# POWERSYSTEM.net
KiCad netlist of a schematic drawn in Altium Designer
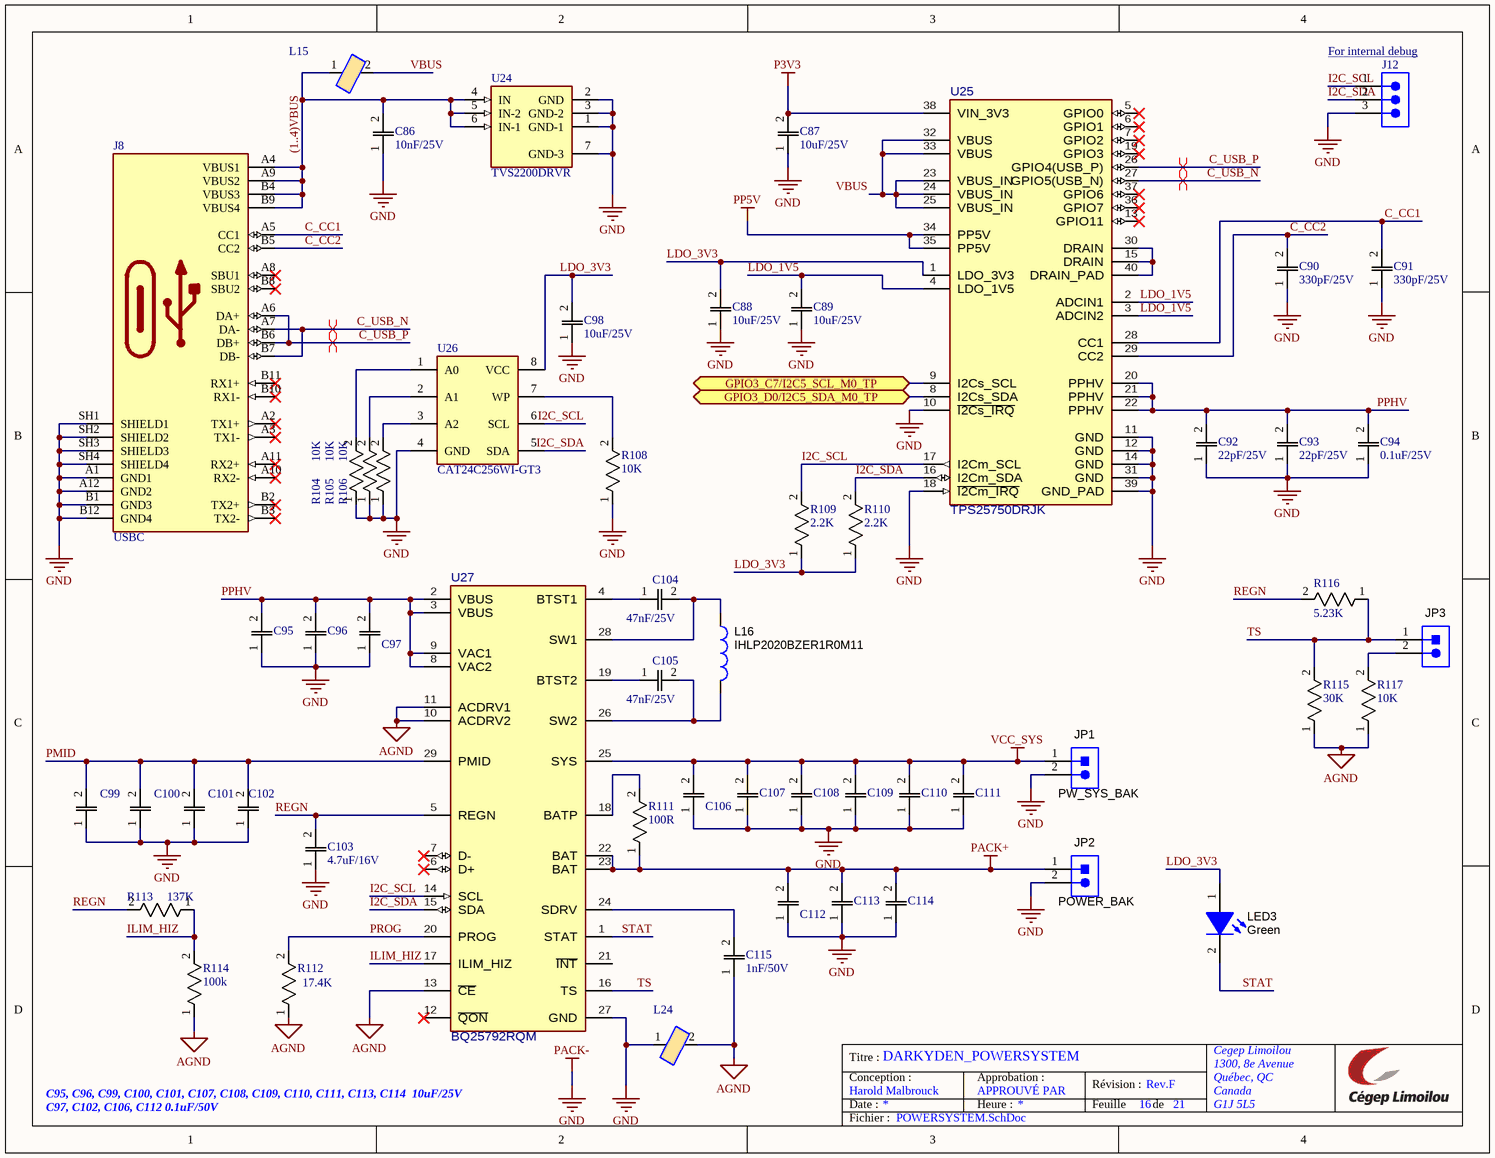
[diagram p0: POWERSYSTEM.SchDoc]

(export (version "E")
  (design (tool "Eeschema 10.0.6"))
  (components
    (comp (ref "C86")
      (value "10nF/25V")
      (footprint "C0805")
      (description "0.01uF 25V X7R 10% SMD 0805 125C Paper T/R")
      (fields
        (field (name "MOUSER PART NUMBER") "80-C0805C103K3R")
        (field (name "ARROW PART NUMBER") "C0805C103K3RACTU")
      )
      (libsource (lib "DARKYDEN") (part "C0805C103K3RACTU"))
    )
    (comp (ref "C87")
      (value "10uF/25V")
      (footprint "C0805")
      (description "10uF / 25 VDC, +85degC, X5R Dielec, +/-10% ¦ KEMET C0805C106K3PACTU 0805")
      (fields
        (field (name "MANUFACTURER") "KEMET")
        (field (name "MANUFACTURER PART NUMBER") "C0805C106K3PACTU")
      )
      (libsource (lib "DARKYDEN") (part "C0805C106K3PACTU"))
    )
    (comp (ref "C88")
      (value "10uF/25V")
      (footprint "C0805")
      (description "10uF / 25 VDC, +85degC, X5R Dielec, +/-10% ¦ KEMET C0805C106K3PACTU 0805")
      (fields
        (field (name "MANUFACTURER") "KEMET")
        (field (name "MANUFACTURER PART NUMBER") "C0805C106K3PACTU")
      )
      (libsource (lib "DARKYDEN") (part "C0805C106K3PACTU"))
    )
    (comp (ref "C89")
      (value "10uF/25V")
      (footprint "C0805")
      (description "10uF / 25 VDC, +85degC, X5R Dielec, +/-10% ¦ KEMET C0805C106K3PACTU 0805")
      (fields
        (field (name "MANUFACTURER") "KEMET")
        (field (name "MANUFACTURER PART NUMBER") "C0805C106K3PACTU")
      )
      (libsource (lib "DARKYDEN") (part "C0805C106K3PACTU"))
    )
    (comp (ref "C90")
      (value "330pF/25V")
      (footprint "SamacSys:C0805")
      (description "330pF 25VC0G 0805 10%")
      (fields (field (name "MOUSER PART NUMBER") "80-C0805C331K3G") (field (name "MANUFACTURER") "KEMET"))
      (libsource (lib "DARKYDEN") (part "C0805C331K3GACTU"))
    )
    (comp (ref "C91")
      (value "330pF/25V")
      (footprint "SamacSys:C0805")
      (description "330pF 25VC0G 0805 10%")
      (fields (field (name "MOUSER PART NUMBER") "80-C0805C331K3G") (field (name "MANUFACTURER") "KEMET"))
      (libsource (lib "DARKYDEN") (part "C0805C331K3GACTU"))
    )
    (comp (ref "C92")
      (value "22pF/25V")
      (footprint "c0805")
      (description "22uF/25V 20% X5R 0805")
      (fields
        (field (name "MOUSER PART NUMBER") "187-CL21A226MAYNNNE")
        (field (name "ARROW PART NUMBER") "CL21A226MAYNNNE")
      )
      (libsource (lib "DARKYDEN") (part "CL21A226MAYNNNE"))
    )
    (comp (ref "C93")
      (value "22pF/25V")
      (footprint "c0805")
      (description "22uF/25V 20% X5R 0805")
      (fields
        (field (name "MOUSER PART NUMBER") "187-CL21A226MAYNNNE")
        (field (name "ARROW PART NUMBER") "CL21A226MAYNNNE")
      )
      (libsource (lib "DARKYDEN") (part "CL21A226MAYNNNE"))
    )
    (comp (ref "C94")
      (value "0.1uF/25V")
      (footprint "c0805")
      (description "0.1uF 25V X7R 10% SMD 0805 125C Plastic T/R")
      (fields
        (field (name "MANUFACTURER") "KEMET")
        (field (name "MANUFACTURER PART NUMBER") "C0805C104K5RACTU")
      )
      (libsource (lib "DARKYDEN") (part "C0805C104K3RACTU"))
    )
    (comp (ref "C95")
      (value "10uF/25V")
      (footprint "C0805")
      (description "10uF / 25 VDC, +85degC, X5R Dielec, +/-10% ¦ KEMET C0805C106K3PACTU 0805")
      (fields
        (field (name "MANUFACTURER") "KEMET")
        (field (name "MANUFACTURER PART NUMBER") "C0805C106K3PACTU")
      )
      (libsource (lib "DARKYDEN") (part "C0805C106K3PACTU"))
    )
    (comp (ref "C96")
      (value "10uF/25V")
      (footprint "C0805")
      (description "10uF / 25 VDC, +85degC, X5R Dielec, +/-10% ¦ KEMET C0805C106K3PACTU 0805")
      (fields
        (field (name "MANUFACTURER") "KEMET")
        (field (name "MANUFACTURER PART NUMBER") "C0805C106K3PACTU")
      )
      (libsource (lib "DARKYDEN") (part "C0805C106K3PACTU"))
    )
    (comp (ref "C97")
      (value "0.1uF/50V")
      (footprint "C0805")
      (description "0.1uF/50V X7R 10% 0805 Multilayer Ceramic Capacitors Mlcc Smd/Smt Rohs")
      (fields
        (field (name "MOUSER PART NUMBER") "80-C0805C104K5R")
        (field (name "ARROW PART NUMBER") "C0805C104K5RACTU")
      )
      (libsource (lib "DARKYDEN") (part "C0805C104K5RACTU"))
    )
    (comp (ref "C98")
      (value "10uF/25V")
      (footprint "C0805")
      (description "10uF / 25 VDC, +85degC, X5R Dielec, +/-10% ¦ KEMET C0805C106K3PACTU 0805")
      (fields
        (field (name "MANUFACTURER") "KEMET")
        (field (name "MANUFACTURER PART NUMBER") "C0805C106K3PACTU")
      )
      (libsource (lib "DARKYDEN") (part "C0805C106K3PACTU"))
    )
    (comp (ref "C99")
      (value "10uF/25V")
      (footprint "C0805")
      (description "10uF / 25 VDC, +85degC, X5R Dielec, +/-10% ¦ KEMET C0805C106K3PACTU 0805")
      (fields
        (field (name "MANUFACTURER") "KEMET")
        (field (name "MANUFACTURER PART NUMBER") "C0805C106K3PACTU")
      )
      (libsource (lib "DARKYDEN") (part "C0805C106K3PACTU"))
    )
    (comp (ref "C100")
      (value "10uF/25V")
      (footprint "C0805")
      (description "10uF / 25 VDC, +85degC, X5R Dielec, +/-10% ¦ KEMET C0805C106K3PACTU 0805")
      (fields
        (field (name "MANUFACTURER") "KEMET")
        (field (name "MANUFACTURER PART NUMBER") "C0805C106K3PACTU")
      )
      (libsource (lib "DARKYDEN") (part "C0805C106K3PACTU"))
    )
    (comp (ref "C101")
      (value "10uF/25V")
      (footprint "C0805")
      (description "10uF / 25 VDC, +85degC, X5R Dielec, +/-10% ¦ KEMET C0805C106K3PACTU 0805")
      (fields
        (field (name "MANUFACTURER") "KEMET")
        (field (name "MANUFACTURER PART NUMBER") "C0805C106K3PACTU")
      )
      (libsource (lib "DARKYDEN") (part "C0805C106K3PACTU"))
    )
    (comp (ref "C102")
      (value "0.1uF/50V")
      (footprint "C0805")
      (description "0.1uF/50V X7R 10% 0805 Multilayer Ceramic Capacitors Mlcc Smd/Smt Rohs")
      (fields
        (field (name "MOUSER PART NUMBER") "80-C0805C104K5R")
        (field (name "ARROW PART NUMBER") "C0805C104K5RACTU")
      )
      (libsource (lib "DARKYDEN") (part "C0805C104K5RACTU"))
    )
    (comp (ref "C103")
      (value "4.7uF/16V")
      (footprint "C0805")
      (description "4.7 uF, 16 V, ± 10%, X7R, 0805 [2012 Metric]")
      (fields
        (field (name "MOUSER PART NUMBER") "80-C0805C475K4R")
        (field (name "ARROW PART NUMBER") "C0805C475K4RACTU")
      )
      (libsource (lib "DARKYDEN") (part "C0805C475K4RACTU"))
    )
    (comp (ref "C104")
      (value "47nF/25V")
      (footprint "C0805")
      (description "47nF/25V C0G 10% Pad SMD 0805 125C Extreme Low ESR T/R")
      (fields
        (field (name "MOUSER PART NUMBER") "80-C0805C473K3G")
        (field (name "ARROW PART NUMBER") "C0805C473K3GACTU")
      )
      (libsource (lib "DARKYDEN") (part "C0805C473K3GACTU"))
    )
    (comp (ref "C105")
      (value "47nF/25V")
      (footprint "C0805")
      (description "47nF/25V C0G 10% Pad SMD 0805 125C Extreme Low ESR T/R")
      (fields
        (field (name "MOUSER PART NUMBER") "80-C0805C473K3G")
        (field (name "ARROW PART NUMBER") "C0805C473K3GACTU")
      )
      (libsource (lib "DARKYDEN") (part "C0805C473K3GACTU"))
    )
    (comp (ref "C106")
      (value "0.1uF/50V")
      (footprint "C0805")
      (description "0.1uF/50V X7R 10% 0805 Multilayer Ceramic Capacitors Mlcc Smd/Smt Rohs")
      (fields
        (field (name "MOUSER PART NUMBER") "80-C0805C104K5R")
        (field (name "ARROW PART NUMBER") "C0805C104K5RACTU")
      )
      (libsource (lib "DARKYDEN") (part "C0805C104K5RACTU"))
    )
    (comp (ref "C107")
      (value "10uF/25V")
      (footprint "C0805")
      (description "10uF / 25 VDC, +85degC, X5R Dielec, +/-10% ¦ KEMET C0805C106K3PACTU 0805")
      (fields
        (field (name "MANUFACTURER") "KEMET")
        (field (name "MANUFACTURER PART NUMBER") "C0805C106K3PACTU")
      )
      (libsource (lib "DARKYDEN") (part "C0805C106K3PACTU"))
    )
    (comp (ref "C108")
      (value "10uF/25V")
      (footprint "C0805")
      (description "10uF / 25 VDC, +85degC, X5R Dielec, +/-10% ¦ KEMET C0805C106K3PACTU 0805")
      (fields
        (field (name "MANUFACTURER") "KEMET")
        (field (name "MANUFACTURER PART NUMBER") "C0805C106K3PACTU")
      )
      (libsource (lib "DARKYDEN") (part "C0805C106K3PACTU"))
    )
    (comp (ref "C109")
      (value "10uF/25V")
      (footprint "C0805")
      (description "10uF / 25 VDC, +85degC, X5R Dielec, +/-10% ¦ KEMET C0805C106K3PACTU 0805")
      (fields
        (field (name "MANUFACTURER") "KEMET")
        (field (name "MANUFACTURER PART NUMBER") "C0805C106K3PACTU")
      )
      (libsource (lib "DARKYDEN") (part "C0805C106K3PACTU"))
    )
    (comp (ref "C110")
      (value "10uF/25V")
      (footprint "C0805")
      (description "10uF / 25 VDC, +85degC, X5R Dielec, +/-10% ¦ KEMET C0805C106K3PACTU 0805")
      (fields
        (field (name "MANUFACTURER") "KEMET")
        (field (name "MANUFACTURER PART NUMBER") "C0805C106K3PACTU")
      )
      (libsource (lib "DARKYDEN") (part "C0805C106K3PACTU"))
    )
    (comp (ref "C111")
      (value "10uF/25V")
      (footprint "C0805")
      (description "10uF / 25 VDC, +85degC, X5R Dielec, +/-10% ¦ KEMET C0805C106K3PACTU 0805")
      (fields
        (field (name "MANUFACTURER") "KEMET")
        (field (name "MANUFACTURER PART NUMBER") "C0805C106K3PACTU")
      )
      (libsource (lib "DARKYDEN") (part "C0805C106K3PACTU"))
    )
    (comp (ref "C112")
      (value "0.1uF/50V")
      (footprint "C0805")
      (description "0.1uF/50V X7R 10% 0805 Multilayer Ceramic Capacitors Mlcc Smd/Smt Rohs")
      (fields
        (field (name "MOUSER PART NUMBER") "80-C0805C104K5R")
        (field (name "ARROW PART NUMBER") "C0805C104K5RACTU")
      )
      (libsource (lib "DARKYDEN") (part "C0805C104K5RACTU"))
    )
    (comp (ref "C113")
      (value "10uF/25V")
      (footprint "C0805")
      (description "10uF / 25 VDC, +85degC, X5R Dielec, +/-10% ¦ KEMET C0805C106K3PACTU 0805")
      (fields
        (field (name "MANUFACTURER") "KEMET")
        (field (name "MANUFACTURER PART NUMBER") "C0805C106K3PACTU")
      )
      (libsource (lib "DARKYDEN") (part "C0805C106K3PACTU"))
    )
    (comp (ref "C114")
      (value "10uF/25V")
      (footprint "C0805")
      (description "10uF / 25 VDC, +85degC, X5R Dielec, +/-10% ¦ KEMET C0805C106K3PACTU 0805")
      (fields
        (field (name "MANUFACTURER") "KEMET")
        (field (name "MANUFACTURER PART NUMBER") "C0805C106K3PACTU")
      )
      (libsource (lib "DARKYDEN") (part "C0805C106K3PACTU"))
    )
    (comp (ref "C115")
      (value "1nF/50V")
      (footprint "C0805")
      (description "Multilayer Ceramic Capacitor 1000 Pf 50 V ½ 10% X7R 0805 [2012 Metric]")
      (fields
        (field (name "MANUFACTURER") "KEMET")
        (field (name "MANUFACTURER PART NUMBER") "C0805C102K5RACTU")
      )
      (libsource (lib "DARKYDEN") (part "C0805C102K5RACTU"))
    )
    (comp (ref "J8")
      (value "USBC")
      (footprint "USB_C")
      (fields (field (name "MF") "Molex") (field (name "MP") "2012670005"))
      (libsource (lib "DARKYDEN") (part "USBC"))
    )
    (comp (ref "J12")
      (value "61300311121")
      (footprint "61300311121")
      (description "WR-PHD Pin Header, THT, Vertical, pitch 2.54mm, 1 Row, 3P")
      (fields (field (name "MANUFACTURER") "Wurth Elektronik"))
      (libsource (lib "Header") (part "61300311121"))
    )
    (comp (ref "JP1")
      (value "PW_SYS_BAK")
      (footprint "61300211121")
      (description "Header, 100mil, 2x1, Tin, TH")
      (fields
        (field (name "PARTNUMBER") "PEC02SAAN")
        (field (name "MANUFACTURER") "Sullins Connector Solutions")
        (field (name "PUBLISHER") "Texas Instruments")
      )
      (libsource (lib "texas_instrument_power") (part "Header_2x1"))
    )
    (comp (ref "JP2")
      (value "POWER_BAK")
      (footprint "61300211121")
      (description "Header, 100mil, 2x1, Tin, TH")
      (fields
        (field (name "PARTNUMBER") "PEC02SAAN")
        (field (name "MANUFACTURER") "Sullins Connector Solutions")
        (field (name "PUBLISHER") "Texas Instruments")
      )
      (libsource (lib "texas_instrument_power") (part "Header_2x1"))
    )
    (comp (ref "JP3")
      (value "TS")
      (footprint "61300211121")
      (description "Header, 100mil, 2x1, Tin, TH")
      (fields
        (field (name "PARTNUMBER") "PEC02SAAN")
        (field (name "MANUFACTURER") "Sullins Connector Solutions")
        (field (name "PUBLISHER") "Texas Instruments")
      )
      (libsource (lib "texas_instrument_power") (part "Header_2x1"))
    )
    (comp (ref "L15")
      (value "FBMJ2125HM210NT")
      (footprint "INDC2012X105N")
      (description "Ferrite Beads Power Chip 21Ohm 30% 100MHz 6A 0.004Ohm DCR 0805 Automotive T/R")
      (fields
        (field (name "MANUFACTURER") "Taiyo Yuden")
        (field (name "MOUSER PART NUMBER") "963-FBMJ2125HM210NT")
      )
      (libsource (lib "SamacSys") (part "FBMJ2125HM210NT"))
    )
    (comp (ref "L16")
      (value "IHLP2020BZER1R0M11")
      (footprint "IHLP-2020BZ")
      (description "Inductor, Shielded Drum Core, Powdered Iron, 1 uH, 7 A, 0.0181 ohm, SMD")
      (fields (field (name "MANUFACTURER") "Vishay-Dale") (field (name "PUBLISHER") "Texas Instruments"))
      (libsource (lib "texas_instrument_power") (part "IHLP2020BZER1R0M11"))
    )
    (comp (ref "L24")
      (value "FBMJ2125HM210NT")
      (footprint "INDC2012X105N")
      (description "Ferrite Beads Power Chip 21Ohm 30% 100MHz 6A 0.004Ohm DCR 0805 Automotive T/R")
      (fields
        (field (name "MANUFACTURER") "Taiyo Yuden")
        (field (name "MOUSER PART NUMBER") "963-FBMJ2125HM210NT")
      )
      (libsource (lib "SamacSys") (part "FBMJ2125HM210NT"))
    )
    (comp (ref "LED3")
      (value "Green")
      (footprint "LED_LTST-C190")
      (description "LED, Green, SMD")
      (fields (field (name "MANUFACTURER") "Lite-On") (field (name "PARTNUMBER") "LTST-C190GKT"))
      (libsource (lib "PD_BQ_Ref_Design") (part "LED_Gr_SMD"))
    )
    (comp (ref "R104")
      (value "10K")
      (footprint "SamacSys:RESC1608X55N")
      (description "10K Ohm 5% Res Thick Film 0603  0.1W(1/10W) ±200ppm/C Pad SMD Automotive T/R")
      (fields
        (field (name "MOUSER PART NUMBER") "667-ERJ-3GEYJ103V")
        (field (name "ARROW PART NUMBER") "ERJ-3GEYJ103V")
      )
      (libsource (lib "DARKYDEN") (part "ERJ-3GEYJ103V"))
    )
    (comp (ref "R105")
      (value "10K")
      (footprint "SamacSys:RESC1608X55N")
      (description "10K Ohm 5% Res Thick Film 0603  0.1W(1/10W) ±200ppm/C Pad SMD Automotive T/R")
      (fields
        (field (name "MOUSER PART NUMBER") "667-ERJ-3GEYJ103V")
        (field (name "ARROW PART NUMBER") "ERJ-3GEYJ103V")
      )
      (libsource (lib "DARKYDEN") (part "ERJ-3GEYJ103V"))
    )
    (comp (ref "R106")
      (value "10K")
      (footprint "SamacSys:RESC1608X55N")
      (description "10K Ohm 5% Res Thick Film 0603  0.1W(1/10W) ±200ppm/C Pad SMD Automotive T/R")
      (fields
        (field (name "MOUSER PART NUMBER") "667-ERJ-3GEYJ103V")
        (field (name "ARROW PART NUMBER") "ERJ-3GEYJ103V")
      )
      (libsource (lib "DARKYDEN") (part "ERJ-3GEYJ103V"))
    )
    (comp (ref "R108")
      (value "10K")
      (footprint "SamacSys:RESC1608X55N")
      (description "10K Ohm 5% Res Thick Film 0603  0.1W(1/10W) ±200ppm/C Pad SMD Automotive T/R")
      (fields
        (field (name "MOUSER PART NUMBER") "667-ERJ-3GEYJ103V")
        (field (name "ARROW PART NUMBER") "ERJ-3GEYJ103V")
      )
      (libsource (lib "DARKYDEN") (part "ERJ-3GEYJ103V"))
    )
    (comp (ref "R109")
      (value "2.2K")
      (footprint "SamacSys:RESC1608X55N")
      (description "2.2 kOhm, ï¿½ 5%, 100 mW, 0603 [1608 Metric], Thick Film, General Purpose")
      (fields
        (field (name "MOUSER PART NUMBER") "667-ERJ-3GEYJ222V")
        (field (name "ARROW PART NUMBER") "ERJ-3GEYJ222V")
      )
      (libsource (lib "DARKYDEN") (part "ERJ-3GEYJ222V"))
    )
    (comp (ref "R110")
      (value "2.2K")
      (footprint "SamacSys:RESC1608X55N")
      (description "2.2 kOhm, ï¿½ 5%, 100 mW, 0603 [1608 Metric], Thick Film, General Purpose")
      (fields
        (field (name "MOUSER PART NUMBER") "667-ERJ-3GEYJ222V")
        (field (name "ARROW PART NUMBER") "ERJ-3GEYJ222V")
      )
      (libsource (lib "DARKYDEN") (part "ERJ-3GEYJ222V"))
    )
    (comp (ref "R111")
      (value "100R")
      (footprint "SamacSys:RESC1608X55N")
      (description "100 Ohm 1% 1/10W 0603 ±100ppm/°C Molded SMD Punched Carrier T/R")
      (fields
        (field (name "MOUSER PART NUMBER") "667-ERJ-3EKF1000V")
        (field (name "ARROW PART NUMBER") "ERJ-3EKF1000V")
      )
      (libsource (lib "DARKYDEN") (part "ERJ-3EKF1000V"))
    )
    (comp (ref "R112")
      (value "17.4K")
      (footprint "SamacSys:RESC1608X55N")
      (description "17.4K Ohm 1% 1/10W +/-100ppm/ßC Molded Res Thick Film 0603  SMD Punched Carrier T/R")
      (fields
        (field (name "MOUSER PART NUMBER") "667-ERJ-3EKF1742V")
        (field (name "ARROW PART NUMBER") "ERJ-3EKF1742V")
      )
      (libsource (lib "DARKYDEN") (part "ERJ-3EKF1742V"))
    )
    (comp (ref "R113")
      (value "137K")
      (footprint "SamacSys:RESC1608X55N")
      (description "137K Ohm 1% 1/10W Res Thick Film 0603 ±100ppm/°C SMD Punched Carrier T/R")
      (fields
        (field (name "MOUSER PART NUMBER") "667-ERJ-3EKF1373V")
        (field (name "ARROW PART NUMBER") "ERJ-3EKF1373V")
      )
      (libsource (lib "DARKYDEN") (part "ERJ-3EKF1373V"))
    )
    (comp (ref "R114")
      (value "100k")
      (footprint "SamacSys:RESC1608X55N")
      (description "100K Ohm 5%  Res Thick Film 0603 1/10W +/-200ppm/ßC Molded SMD Punched Carrier T/R")
      (fields
        (field (name "MOUSER PART NUMBER") "667-ERJ-3GEYJ104V")
        (field (name "ARROW PART NUMBER") "ERJ-3GEYJ104V")
      )
      (libsource (lib "DARKYDEN") (part "ERJ-3GEYJ104V"))
    )
    (comp (ref "R115")
      (value "30K")
      (footprint "SamacSys:RESC1608X55N")
      (description "30K Ohm 5% 0.1W(1/10W) +/-200ppm/ßC Res Thick Film 0603  SMD Automotive T/R")
      (fields
        (field (name "MOUSER PART NUMBER") "667-ERJ-3GEYJ303V")
        (field (name "MANUFACTURER") "Panasonic")
      )
      (libsource (lib "DARKYDEN") (part "ERJ-3GEYJ303V"))
    )
    (comp (ref "R116")
      (value "5.23K")
      (footprint "SamacSys:RESC1608X55N")
      (description "5.23K Ohm 1% 1/10W Res Thick Film 0603+/-100ppm/ßC Molded SMD Punched Carrier T/R")
      (fields
        (field (name "MOUSER PART NUMBER") "667-ERJ-3EKF5231V")
        (field (name "ARROW PART NUMBER") "ERJ-3EKF5231V")
      )
      (libsource (lib "DARKYDEN") (part "ERJ-3EKF5231V"))
    )
    (comp (ref "R117")
      (value "10K")
      (footprint "SamacSys:RESC1608X55N")
      (description "10K Ohm 5% Res Thick Film 0603  0.1W(1/10W) ±200ppm/C Pad SMD Automotive T/R")
      (fields
        (field (name "MOUSER PART NUMBER") "667-ERJ-3GEYJ103V")
        (field (name "ARROW PART NUMBER") "ERJ-3GEYJ103V")
      )
      (libsource (lib "DARKYDEN") (part "ERJ-3GEYJ103V"))
    )
    (comp (ref "U24")
      (value "TVS2200DRVR")
      (footprint "SON65P200X200X80-7N")
      (description "ESD Suppressors / TVS Diodes 22V flat-clamp surge protection device 6-WSON -40 to 125")
      (fields (field (name "MF") "Texas Instruments"))
      (libsource (lib "TVS2200") (part "TVS2200DRVR"))
    )
    (comp (ref "U25")
      (value "TPS25750DRJK")
      (footprint "RJK0038B-C01-MFG")
      (description "USB Type-C and USB PD Controller with Integrated Power Switches Optimized for Power Applications")
      (fields (field (name "MANUFACTURER") "Texas Instruments"))
      (libsource (lib "PD_BQ_Ref_Design") (part "TPS25750DRJK"))
    )
    (comp (ref "U26")
      (value "CAT24C256WI-GT3")
      (footprint "SOIC127P600X175-8N")
      (description "EEPROM Memory IC 256Kbit I2C 1 MHz 500 ns 8-SOIC")
      (fields (field (name "MOUSER PART NUMBER") "698-CAT24C256WI-GT3"))
      (libsource (lib "SamacSys") (part "CAT24C256WI-GT3"))
    )
    (comp (ref "U27")
      (value "BQ25792RQM")
      (footprint "RQM0029A-MFG")
      (description "BQ2579x HotRod")
      (fields (field (name "MANUFACTURER") "Texas Instruments"))
      (libsource (lib "PD_BQ_Ref_Design") (part "BQ2579x"))
    )
  )
  (nets
    (net (code "1") (name "/(1..4)VBUS") (class "Default")
      (node (ref "C86") (pin "2") (pinfunction "2_2") (pintype "passive"))
      (node (ref "J8") (pin "A4") (pinfunction "VBUS1_A4") (pintype "power_in"))
      (node (ref "J8") (pin "A9") (pinfunction "VBUS2_A9") (pintype "power_in"))
      (node (ref "J8") (pin "B4") (pinfunction "VBUS3_B4") (pintype "power_in"))
      (node (ref "J8") (pin "B9") (pinfunction "VBUS4_B9") (pintype "power_in"))
      (node (ref "L15") (pin "1") (pinfunction "1_1") (pintype "passive"))
      (node (ref "U24") (pin "4") (pinfunction "IN_4") (pintype "input"))
      (node (ref "U24") (pin "5") (pinfunction "IN-2_5") (pintype "input"))
      (node (ref "U24") (pin "6") (pinfunction "IN-1_6") (pintype "input"))
    )
    (net (code "2") (name "/C_CC1") (class "Default")
      (node (ref "C91") (pin "2") (pinfunction "2_2") (pintype "passive"))
      (node (ref "J8") (pin "A5") (pinfunction "CC1_A5") (pintype "bidirectional"))
      (node (ref "U25") (pin "28") (pinfunction "CC1_28") (pintype "passive"))
    )
    (net (code "3") (name "/C_CC2") (class "Default")
      (node (ref "C90") (pin "2") (pinfunction "2_2") (pintype "passive"))
      (node (ref "J8") (pin "B5") (pinfunction "CC2_B5") (pintype "bidirectional"))
      (node (ref "U25") (pin "29") (pinfunction "CC2_29") (pintype "passive"))
    )
    (net (code "4") (name "/C_USB_N") (class "Default")
      (node (ref "J8") (pin "A7") (pinfunction "DA-_A7") (pintype "bidirectional"))
      (node (ref "J8") (pin "B7") (pinfunction "DB-_B7") (pintype "bidirectional"))
      (node (ref "U25") (pin "27") (pinfunction "GPIO5(USB_N)_27") (pintype "bidirectional"))
    )
    (net (code "5") (name "/C_USB_P") (class "Default")
      (node (ref "J8") (pin "A6") (pinfunction "DA+_A6") (pintype "bidirectional"))
      (node (ref "J8") (pin "B6") (pinfunction "DB+_B6") (pintype "bidirectional"))
      (node (ref "U25") (pin "26") (pinfunction "GPIO4(USB_P)_26") (pintype "bidirectional"))
    )
    (net (code "6") (name "/GPIO3_C7{slash}I2C5_SCL_M0_TP") (class "Default")
      (node (ref "U25") (pin "9") (pinfunction "I2Cs_SCL_9") (pintype "passive"))
    )
    (net (code "7") (name "/GPIO3_D0{slash}I2C5_SDA_M0_TP") (class "Default")
      (node (ref "U25") (pin "8") (pinfunction "I2Cs_SDA_8") (pintype "passive"))
    )
    (net (code "8") (name "/I2C_SCL") (class "Default")
      (node (ref "J12") (pin "1") (pinfunction "1_1") (pintype "passive"))
      (node (ref "R109") (pin "2") (pinfunction "2_2") (pintype "passive"))
      (node (ref "U25") (pin "17") (pinfunction "I2Cm_SCL_17") (pintype "output"))
      (node (ref "U26") (pin "6") (pinfunction "SCL_6") (pintype "passive"))
      (node (ref "U27") (pin "14") (pinfunction "SCL_14") (pintype "input"))
    )
    (net (code "9") (name "/I2C_SDA") (class "Default")
      (node (ref "J12") (pin "2") (pinfunction "2_2") (pintype "passive"))
      (node (ref "R110") (pin "2") (pinfunction "2_2") (pintype "passive"))
      (node (ref "U25") (pin "16") (pinfunction "I2Cm_SDA_16") (pintype "bidirectional"))
      (node (ref "U26") (pin "5") (pinfunction "SDA_5") (pintype "passive"))
      (node (ref "U27") (pin "15") (pinfunction "SDA_15") (pintype "bidirectional"))
    )
    (net (code "10") (name "/ILIM_HIZ") (class "Default")
      (node (ref "R113") (pin "1") (pinfunction "1_1") (pintype "passive"))
      (node (ref "R114") (pin "2") (pinfunction "2_2") (pintype "passive"))
      (node (ref "U27") (pin "17") (pinfunction "ILIM_HIZ_17") (pintype "passive"))
    )
    (net (code "11") (name "/LDO_1V5") (class "Default")
      (node (ref "C89") (pin "2") (pinfunction "2_2") (pintype "passive"))
      (node (ref "U25") (pin "2") (pinfunction "ADCIN1_2") (pintype "passive"))
      (node (ref "U25") (pin "3") (pinfunction "ADCIN2_3") (pintype "passive"))
      (node (ref "U25") (pin "4") (pinfunction "LDO_1V5_4") (pintype "passive"))
    )
    (net (code "12") (name "/LDO_3V3") (class "Default")
      (node (ref "C88") (pin "2") (pinfunction "2_2") (pintype "passive"))
      (node (ref "C98") (pin "2") (pinfunction "2_2") (pintype "passive"))
      (node (ref "LED3") (pin "1") (pinfunction "A_1") (pintype "passive"))
      (node (ref "R109") (pin "1") (pinfunction "1_1") (pintype "passive"))
      (node (ref "R110") (pin "1") (pinfunction "1_1") (pintype "passive"))
      (node (ref "U25") (pin "1") (pinfunction "LDO_3V3_1") (pintype "passive"))
      (node (ref "U26") (pin "8") (pinfunction "VCC_8") (pintype "passive"))
    )
    (net (code "13") (name "/PMID") (class "Default")
      (node (ref "C100") (pin "2") (pinfunction "2_2") (pintype "passive"))
      (node (ref "C101") (pin "2") (pinfunction "2_2") (pintype "passive"))
      (node (ref "C102") (pin "2") (pinfunction "2_2") (pintype "passive"))
      (node (ref "C99") (pin "2") (pinfunction "2_2") (pintype "passive"))
      (node (ref "U27") (pin "29") (pinfunction "PMID_29") (pintype "passive"))
    )
    (net (code "14") (name "/PPHV") (class "Default")
      (node (ref "C92") (pin "2") (pinfunction "2_2") (pintype "passive"))
      (node (ref "C93") (pin "2") (pinfunction "2_2") (pintype "passive"))
      (node (ref "C94") (pin "2") (pinfunction "2_2") (pintype "passive"))
      (node (ref "C95") (pin "2") (pinfunction "2_2") (pintype "passive"))
      (node (ref "C96") (pin "2") (pinfunction "2_2") (pintype "passive"))
      (node (ref "C97") (pin "2") (pinfunction "2_2") (pintype "passive"))
      (node (ref "U25") (pin "20") (pinfunction "PPHV_20") (pintype "passive"))
      (node (ref "U25") (pin "21") (pinfunction "PPHV_21") (pintype "passive"))
      (node (ref "U25") (pin "22") (pinfunction "PPHV_22") (pintype "passive"))
      (node (ref "U27") (pin "2") (pinfunction "VBUS_2") (pintype "power_in"))
      (node (ref "U27") (pin "3") (pinfunction "VBUS_3") (pintype "power_in"))
      (node (ref "U27") (pin "8") (pinfunction "VAC2_8") (pintype "power_in"))
      (node (ref "U27") (pin "9") (pinfunction "VAC1_9") (pintype "power_in"))
    )
    (net (code "15") (name "/PROG") (class "Default")
      (node (ref "R112") (pin "2") (pinfunction "2_2") (pintype "passive"))
      (node (ref "U27") (pin "20") (pinfunction "PROG_20") (pintype "passive"))
    )
    (net (code "16") (name "/REGN") (class "Default")
      (node (ref "C103") (pin "2") (pinfunction "2_2") (pintype "passive"))
      (node (ref "R113") (pin "2") (pinfunction "2_2") (pintype "passive"))
      (node (ref "R116") (pin "2") (pinfunction "2_2") (pintype "passive"))
      (node (ref "U27") (pin "5") (pinfunction "REGN_5") (pintype "passive"))
    )
    (net (code "17") (name "/STAT") (class "Default")
      (node (ref "LED3") (pin "2") (pinfunction "K_2") (pintype "passive"))
      (node (ref "U27") (pin "1") (pinfunction "STAT_1") (pintype "passive"))
    )
    (net (code "18") (name "/TS") (class "Default")
      (node (ref "JP3") (pin "1") (pinfunction "1_1") (pintype "passive"))
      (node (ref "R115") (pin "2") (pinfunction "2_2") (pintype "passive"))
      (node (ref "R116") (pin "1") (pinfunction "1_1") (pintype "passive"))
      (node (ref "U27") (pin "16") (pinfunction "TS_16") (pintype "passive"))
    )
    (net (code "19") (name "/VBUS") (class "Default")
      (node (ref "L15") (pin "2") (pinfunction "2_2") (pintype "passive"))
      (node (ref "U25") (pin "23") (pinfunction "VBUS_IN_23") (pintype "power_in"))
      (node (ref "U25") (pin "24") (pinfunction "VBUS_IN_24") (pintype "power_in"))
      (node (ref "U25") (pin "25") (pinfunction "VBUS_IN_25") (pintype "power_in"))
      (node (ref "U25") (pin "32") (pinfunction "VBUS_32") (pintype "power_in"))
      (node (ref "U25") (pin "33") (pinfunction "VBUS_33") (pintype "power_in"))
    )
    (net (code "20") (name "AGND") (class "Default")
      (node (ref "C115") (pin "1") (pinfunction "1_1") (pintype "passive"))
      (node (ref "L24") (pin "2") (pinfunction "2_2") (pintype "passive"))
      (node (ref "R112") (pin "1") (pinfunction "1_1") (pintype "passive"))
      (node (ref "R114") (pin "1") (pinfunction "1_1") (pintype "passive"))
      (node (ref "R115") (pin "1") (pinfunction "1_1") (pintype "passive"))
      (node (ref "R117") (pin "1") (pinfunction "1_1") (pintype "passive"))
      (node (ref "U27") (pin "10") (pinfunction "ACDRV2_10") (pintype "power_in"))
      (node (ref "U27") (pin "11") (pinfunction "ACDRV1_11") (pintype "power_in"))
      (node (ref "U27") (pin "13") (pinfunction "~{CE}_13") (pintype "passive"))
    )
    (net (code "21") (name "GND") (class "Default")
      (node (ref "C100") (pin "1") (pinfunction "1_1") (pintype "passive"))
      (node (ref "C101") (pin "1") (pinfunction "1_1") (pintype "passive"))
      (node (ref "C102") (pin "1") (pinfunction "1_1") (pintype "passive"))
      (node (ref "C103") (pin "1") (pinfunction "1_1") (pintype "passive"))
      (node (ref "C106") (pin "1") (pinfunction "1_1") (pintype "passive"))
      (node (ref "C107") (pin "1") (pinfunction "1_1") (pintype "passive"))
      (node (ref "C108") (pin "1") (pinfunction "1_1") (pintype "passive"))
      (node (ref "C109") (pin "1") (pinfunction "1_1") (pintype "passive"))
      (node (ref "C110") (pin "1") (pinfunction "1_1") (pintype "passive"))
      (node (ref "C111") (pin "1") (pinfunction "1_1") (pintype "passive"))
      (node (ref "C112") (pin "1") (pinfunction "1_1") (pintype "passive"))
      (node (ref "C113") (pin "1") (pinfunction "1_1") (pintype "passive"))
      (node (ref "C114") (pin "1") (pinfunction "1_1") (pintype "passive"))
      (node (ref "C86") (pin "1") (pinfunction "1_1") (pintype "passive"))
      (node (ref "C87") (pin "1") (pinfunction "1_1") (pintype "passive"))
      (node (ref "C88") (pin "1") (pinfunction "1_1") (pintype "passive"))
      (node (ref "C89") (pin "1") (pinfunction "1_1") (pintype "passive"))
      (node (ref "C90") (pin "1") (pinfunction "1_1") (pintype "passive"))
      (node (ref "C91") (pin "1") (pinfunction "1_1") (pintype "passive"))
      (node (ref "C92") (pin "1") (pinfunction "1_1") (pintype "passive"))
      (node (ref "C93") (pin "1") (pinfunction "1_1") (pintype "passive"))
      (node (ref "C94") (pin "1") (pinfunction "1_1") (pintype "passive"))
      (node (ref "C95") (pin "1") (pinfunction "1_1") (pintype "passive"))
      (node (ref "C96") (pin "1") (pinfunction "1_1") (pintype "passive"))
      (node (ref "C97") (pin "1") (pinfunction "1_1") (pintype "passive"))
      (node (ref "C98") (pin "1") (pinfunction "1_1") (pintype "passive"))
      (node (ref "C99") (pin "1") (pinfunction "1_1") (pintype "passive"))
      (node (ref "J12") (pin "3") (pinfunction "3_3") (pintype "passive"))
      (node (ref "J8") (pin "A1") (pinfunction "GND1_A1") (pintype "passive"))
      (node (ref "J8") (pin "A12") (pinfunction "GND2_A12") (pintype "passive"))
      (node (ref "J8") (pin "B1") (pinfunction "GND3_B1") (pintype "passive"))
      (node (ref "J8") (pin "B12") (pinfunction "GND4_B12") (pintype "passive"))
      (node (ref "J8") (pin "SH1") (pinfunction "SHIELD1_SH1") (pintype "passive"))
      (node (ref "J8") (pin "SH2") (pinfunction "SHIELD2_SH2") (pintype "passive"))
      (node (ref "J8") (pin "SH3") (pinfunction "SHIELD3_SH3") (pintype "passive"))
      (node (ref "J8") (pin "SH4") (pinfunction "SHIELD4_SH4") (pintype "passive"))
      (node (ref "JP1") (pin "2") (pinfunction "2_2") (pintype "passive"))
      (node (ref "JP2") (pin "2") (pinfunction "2_2") (pintype "passive"))
      (node (ref "L24") (pin "1") (pinfunction "1_1") (pintype "passive"))
      (node (ref "R104") (pin "1") (pinfunction "1_1") (pintype "passive"))
      (node (ref "R105") (pin "1") (pinfunction "1_1") (pintype "passive"))
      (node (ref "R106") (pin "1") (pinfunction "1_1") (pintype "passive"))
      (node (ref "R108") (pin "1") (pinfunction "1_1") (pintype "passive"))
      (node (ref "U24") (pin "1") (pinfunction "GND-1_1") (pintype "passive"))
      (node (ref "U24") (pin "2") (pinfunction "GND_2") (pintype "passive"))
      (node (ref "U24") (pin "3") (pinfunction "GND-2_3") (pintype "passive"))
      (node (ref "U24") (pin "7") (pinfunction "GND-3_7") (pintype "passive"))
      (node (ref "U25") (pin "10") (pinfunction "~{I2Cs_IRQ}_10") (pintype "passive"))
      (node (ref "U25") (pin "11") (pinfunction "GND_11") (pintype "passive"))
      (node (ref "U25") (pin "12") (pinfunction "GND_12") (pintype "passive"))
      (node (ref "U25") (pin "14") (pinfunction "GND_14") (pintype "passive"))
      (node (ref "U25") (pin "18") (pinfunction "~{I2Cm_IRQ}_18") (pintype "input"))
      (node (ref "U25") (pin "31") (pinfunction "GND_31") (pintype "passive"))
      (node (ref "U25") (pin "39") (pinfunction "GND_PAD_39") (pintype "passive"))
      (node (ref "U26") (pin "4") (pinfunction "GND_4") (pintype "passive"))
      (node (ref "U27") (pin "27") (pinfunction "GND_27") (pintype "power_in"))
    )
    (net (code "22") (name "Net-(JP3-Pad2)") (class "Default")
      (node (ref "JP3") (pin "2") (pinfunction "2_2") (pintype "passive"))
      (node (ref "R117") (pin "2") (pinfunction "2_2") (pintype "passive"))
    )
    (net (code "23") (name "Net-(U25-DRAIN_PAD)") (class "Default")
      (node (ref "U25") (pin "15") (pinfunction "DRAIN_15") (pintype "passive"))
      (node (ref "U25") (pin "30") (pinfunction "DRAIN_30") (pintype "passive"))
      (node (ref "U25") (pin "40") (pinfunction "DRAIN_PAD_40") (pintype "passive"))
    )
    (net (code "24") (name "Net-(U26-A0)") (class "Default")
      (node (ref "R104") (pin "2") (pinfunction "2_2") (pintype "passive"))
      (node (ref "U26") (pin "1") (pinfunction "A0_1") (pintype "passive"))
    )
    (net (code "25") (name "Net-(U26-A1)") (class "Default")
      (node (ref "R105") (pin "2") (pinfunction "2_2") (pintype "passive"))
      (node (ref "U26") (pin "2") (pinfunction "A1_2") (pintype "passive"))
    )
    (net (code "26") (name "Net-(U26-A2)") (class "Default")
      (node (ref "R106") (pin "2") (pinfunction "2_2") (pintype "passive"))
      (node (ref "U26") (pin "3") (pinfunction "A2_3") (pintype "passive"))
    )
    (net (code "27") (name "Net-(U26-WP)") (class "Default")
      (node (ref "R108") (pin "2") (pinfunction "2_2") (pintype "passive"))
      (node (ref "U26") (pin "7") (pinfunction "WP_7") (pintype "passive"))
    )
    (net (code "28") (name "Net-(U27-BATP)") (class "Default")
      (node (ref "R111") (pin "2") (pinfunction "2_2") (pintype "passive"))
      (node (ref "U27") (pin "18") (pinfunction "BATP_18") (pintype "passive"))
    )
    (net (code "29") (name "Net-(U27-BTST1)") (class "Default")
      (node (ref "C104") (pin "1") (pinfunction "1_1") (pintype "passive"))
      (node (ref "U27") (pin "4") (pinfunction "BTST1_4") (pintype "passive"))
    )
    (net (code "30") (name "Net-(U27-BTST2)") (class "Default")
      (node (ref "C105") (pin "1") (pinfunction "1_1") (pintype "passive"))
      (node (ref "U27") (pin "19") (pinfunction "BTST2_19") (pintype "passive"))
    )
    (net (code "31") (name "Net-(U27-SDRV)") (class "Default")
      (node (ref "C115") (pin "2") (pinfunction "2_2") (pintype "passive"))
      (node (ref "U27") (pin "24") (pinfunction "SDRV_24") (pintype "passive"))
    )
    (net (code "32") (name "Net-(U27-SW1)") (class "Default")
      (node (ref "C104") (pin "2") (pinfunction "2_2") (pintype "passive"))
      (node (ref "L16") (pin "1") (pinfunction "1_1") (pintype "passive"))
      (node (ref "U27") (pin "28") (pinfunction "SW1_28") (pintype "passive"))
    )
    (net (code "33") (name "Net-(U27-SW2)") (class "Default")
      (node (ref "C105") (pin "2") (pinfunction "2_2") (pintype "passive"))
      (node (ref "L16") (pin "2") (pinfunction "2_2") (pintype "passive"))
      (node (ref "U27") (pin "26") (pinfunction "SW2_26") (pintype "passive"))
    )
    (net (code "34") (name "P3V3") (class "Default")
      (node (ref "C87") (pin "2") (pinfunction "2_2") (pintype "passive"))
      (node (ref "U25") (pin "38") (pinfunction "VIN_3V3_38") (pintype "power_in"))
    )
    (net (code "35") (name "PACK+") (class "Default")
      (node (ref "C112") (pin "2") (pinfunction "2_2") (pintype "passive"))
      (node (ref "C113") (pin "2") (pinfunction "2_2") (pintype "passive"))
      (node (ref "C114") (pin "2") (pinfunction "2_2") (pintype "passive"))
      (node (ref "JP2") (pin "1") (pinfunction "1_1") (pintype "passive"))
      (node (ref "R111") (pin "1") (pinfunction "1_1") (pintype "passive"))
      (node (ref "U27") (pin "22") (pinfunction "BAT_22") (pintype "passive"))
      (node (ref "U27") (pin "23") (pinfunction "BAT_23") (pintype "passive"))
    )
    (net (code "36") (name "PP5V") (class "Default")
      (node (ref "U25") (pin "34") (pinfunction "PP5V_34") (pintype "power_in"))
      (node (ref "U25") (pin "35") (pinfunction "PP5V_35") (pintype "power_in"))
    )
    (net (code "37") (name "VCC_SYS") (class "Default")
      (node (ref "C106") (pin "2") (pinfunction "2_2") (pintype "passive"))
      (node (ref "C107") (pin "2") (pinfunction "2_2") (pintype "passive"))
      (node (ref "C108") (pin "2") (pinfunction "2_2") (pintype "passive"))
      (node (ref "C109") (pin "2") (pinfunction "2_2") (pintype "passive"))
      (node (ref "C110") (pin "2") (pinfunction "2_2") (pintype "passive"))
      (node (ref "C111") (pin "2") (pinfunction "2_2") (pintype "passive"))
      (node (ref "JP1") (pin "1") (pinfunction "1_1") (pintype "passive"))
      (node (ref "U27") (pin "25") (pinfunction "SYS_25") (pintype "passive"))
    )
    (net (code "38") (name "unconnected-(J8-RX1+-PadB11)") (class "Default")
      (node (ref "J8") (pin "B11") (pinfunction "RX1+_B11") (pintype "input+no_connect"))
    )
    (net (code "39") (name "unconnected-(J8-RX1--PadB10)") (class "Default")
      (node (ref "J8") (pin "B10") (pinfunction "RX1-_B10") (pintype "input+no_connect"))
    )
    (net (code "40") (name "unconnected-(J8-RX2+-PadA11)") (class "Default")
      (node (ref "J8") (pin "A11") (pinfunction "RX2+_A11") (pintype "input+no_connect"))
    )
    (net (code "41") (name "unconnected-(J8-RX2--PadA10)") (class "Default")
      (node (ref "J8") (pin "A10") (pinfunction "RX2-_A10") (pintype "input+no_connect"))
    )
    (net (code "42") (name "unconnected-(J8-SBU1-PadA8)") (class "Default")
      (node (ref "J8") (pin "A8") (pinfunction "SBU1_A8") (pintype "bidirectional+no_connect"))
    )
    (net (code "43") (name "unconnected-(J8-SBU2-PadB8)") (class "Default")
      (node (ref "J8") (pin "B8") (pinfunction "SBU2_B8") (pintype "bidirectional+no_connect"))
    )
    (net (code "44") (name "unconnected-(J8-TX1+-PadA2)") (class "Default")
      (node (ref "J8") (pin "A2") (pinfunction "TX1+_A2") (pintype "output+no_connect"))
    )
    (net (code "45") (name "unconnected-(J8-TX1--PadA3)") (class "Default")
      (node (ref "J8") (pin "A3") (pinfunction "TX1-_A3") (pintype "output+no_connect"))
    )
    (net (code "46") (name "unconnected-(J8-TX2+-PadB2)") (class "Default")
      (node (ref "J8") (pin "B2") (pinfunction "TX2+_B2") (pintype "output+no_connect"))
    )
    (net (code "47") (name "unconnected-(J8-TX2--PadB3)") (class "Default")
      (node (ref "J8") (pin "B3") (pinfunction "TX2-_B3") (pintype "output+no_connect"))
    )
    (net (code "48") (name "unconnected-(U25-GPIO0-Pad5)") (class "Default")
      (node (ref "U25") (pin "5") (pinfunction "GPIO0_5") (pintype "bidirectional+no_connect"))
    )
    (net (code "49") (name "unconnected-(U25-GPIO1-Pad6)") (class "Default")
      (node (ref "U25") (pin "6") (pinfunction "GPIO1_6") (pintype "bidirectional+no_connect"))
    )
    (net (code "50") (name "unconnected-(U25-GPIO2-Pad7)") (class "Default")
      (node (ref "U25") (pin "7") (pinfunction "GPIO2_7") (pintype "bidirectional+no_connect"))
    )
    (net (code "51") (name "unconnected-(U25-GPIO3-Pad19)") (class "Default")
      (node (ref "U25") (pin "19") (pinfunction "GPIO3_19") (pintype "bidirectional+no_connect"))
    )
    (net (code "52") (name "unconnected-(U25-GPIO6-Pad37)") (class "Default")
      (node (ref "U25") (pin "37") (pinfunction "GPIO6_37") (pintype "bidirectional+no_connect"))
    )
    (net (code "53") (name "unconnected-(U25-GPIO7-Pad36)") (class "Default")
      (node (ref "U25") (pin "36") (pinfunction "GPIO7_36") (pintype "bidirectional+no_connect"))
    )
    (net (code "54") (name "unconnected-(U25-GPIO11-Pad13)") (class "Default")
      (node (ref "U25") (pin "13") (pinfunction "GPIO11_13") (pintype "bidirectional+no_connect"))
    )
    (net (code "55") (name "unconnected-(U27-D+-Pad6)") (class "Default")
      (node (ref "U27") (pin "6") (pinfunction "D+_6") (pintype "bidirectional+no_connect"))
    )
    (net (code "56") (name "unconnected-(U27-D--Pad7)") (class "Default")
      (node (ref "U27") (pin "7") (pinfunction "D-_7") (pintype "bidirectional+no_connect"))
    )
    (net (code "57") (name "unconnected-(U27-~{INT}-Pad21)") (class "Default")
      (node (ref "U27") (pin "21") (pinfunction "~{INT}_21") (pintype "passive"))
    )
    (net (code "58") (name "unconnected-(U27-~{QON}-Pad12)") (class "Default")
      (node (ref "U27") (pin "12") (pinfunction "~{QON}_12") (pintype "passive+no_connect"))
    )
  )
)
